# simplePDschematicsv2_AZ_SMD.net
KiCad netlist of a schematic drawn in EAGLE
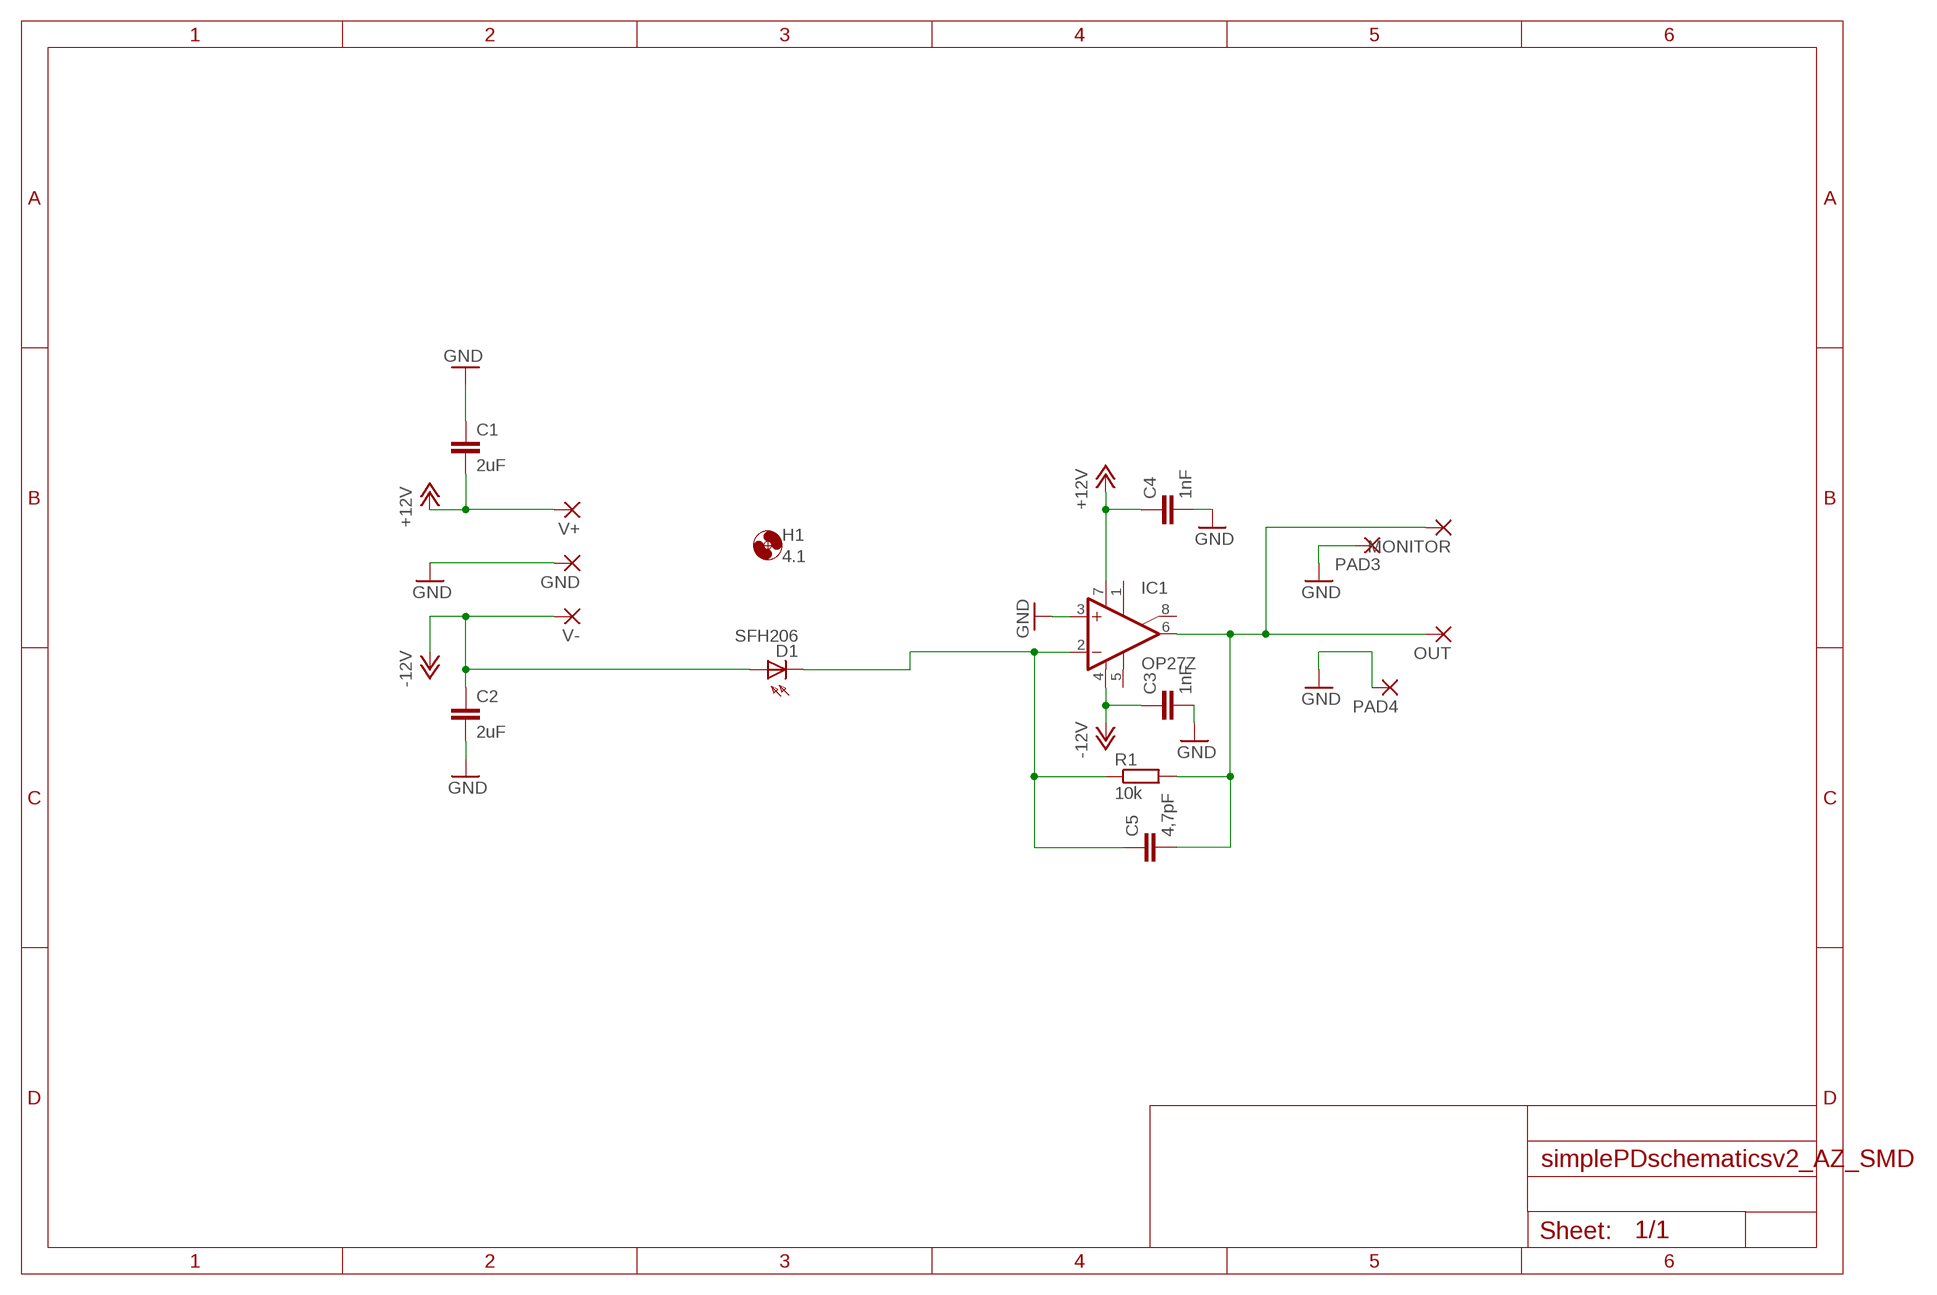
[diagram p0: schematic, sheet 1]

(export (version "E")
  (design (tool "Eeschema 10.0.6"))
  (components
    (comp (ref "C1")
      (value "2uF")
      (footprint "eagle-import:C050-075X075")
      (libsource (lib "eagle-import") (part "C-EU050-075X075"))
    )
    (comp (ref "C2")
      (value "2uF")
      (footprint "eagle-import:C050-075X075")
      (libsource (lib "eagle-import") (part "C-EU050-075X075"))
    )
    (comp (ref "C3")
      (value "1nF")
      (footprint "eagle-import:C025-050X050")
      (libsource (lib "eagle-import") (part "C-EU025-050X050"))
    )
    (comp (ref "C4")
      (value "1nF")
      (footprint "eagle-import:C025-050X050")
      (libsource (lib "eagle-import") (part "C-EU025-050X050"))
    )
    (comp (ref "C5")
      (value "4,7pF")
      (footprint "eagle-import:C025-050X050")
      (libsource (lib "eagle-import") (part "C-EU025-050X050"))
    )
    (comp (ref "D1")
      (value "SFH206")
      (footprint "eagle-import:SFH206")
      (fields (field (name "MPN") "SFH206K"))
      (libsource (lib "eagle-import") (part "SFH206"))
    )
    (comp (ref "GND")
      (value "1,6/0,9")
      (footprint "eagle-import:1,6_0,9")
      (libsource (lib "eagle-import") (part "1,6/0,9"))
    )
    (comp (ref "H1")
      (value "4.1")
      (footprint "eagle-import:4,1")
      (libsource (lib "eagle-import") (part "MOUNT-HOLE4.1"))
    )
    (comp (ref "IC1")
      (value "OP27Z")
      (footprint "eagle-import:DIL08")
      (libsource (lib "eagle-import") (part "OP27Z"))
    )
    (comp (ref "MONITOR")
      (value "1,6/0,9")
      (footprint "eagle-import:1,6_0,9")
      (libsource (lib "eagle-import") (part "1,6/0,9"))
    )
    (comp (ref "OUT")
      (value "1,6/0,9")
      (footprint "eagle-import:1,6_0,9")
      (libsource (lib "eagle-import") (part "1,6/0,9"))
    )
    (comp (ref "PAD3")
      (value "1,6/0,9")
      (footprint "eagle-import:1,6_0,9")
      (libsource (lib "eagle-import") (part "1,6/0,9"))
    )
    (comp (ref "PAD4")
      (value "1,6/0,9")
      (footprint "eagle-import:1,6_0,9")
      (libsource (lib "eagle-import") (part "1,6/0,9"))
    )
    (comp (ref "R1")
      (value "10k")
      (footprint "eagle-import:M1206")
      (libsource (lib "eagle-import") (part "R-EU_M1206"))
    )
    (comp (ref "V+")
      (value "1,6/0,9")
      (footprint "eagle-import:1,6_0,9")
      (libsource (lib "eagle-import") (part "1,6/0,9"))
    )
    (comp (ref "V-")
      (value "1,6/0,9")
      (footprint "eagle-import:1,6_0,9")
      (libsource (lib "eagle-import") (part "1,6/0,9"))
    )
  )
  (nets
    (net (code "1") (name "+12V") (class "Default")
      (node (ref "C1") (pin "2") (pinfunction "2_2") (pintype "passive"))
      (node (ref "C4") (pin "1") (pinfunction "1_1") (pintype "passive"))
      (node (ref "IC1") (pin "7") (pinfunction "V+_7") (pintype "power_in"))
      (node (ref "V+") (pin "1") (pinfunction "P_1") (pintype "passive"))
    )
    (net (code "2") (name "-12V") (class "Default")
      (node (ref "C2") (pin "1") (pinfunction "1_1") (pintype "passive"))
      (node (ref "C3") (pin "1") (pinfunction "1_1") (pintype "passive"))
      (node (ref "D1") (pin "A") (pinfunction "A_A") (pintype "passive"))
      (node (ref "IC1") (pin "4") (pinfunction "V-_4") (pintype "power_in"))
      (node (ref "V-") (pin "1") (pinfunction "P_1") (pintype "passive"))
    )
    (net (code "3") (name "GND") (class "Default")
      (node (ref "C1") (pin "1") (pinfunction "1_1") (pintype "passive"))
      (node (ref "C2") (pin "2") (pinfunction "2_2") (pintype "passive"))
      (node (ref "C3") (pin "2") (pinfunction "2_2") (pintype "passive"))
      (node (ref "C4") (pin "2") (pinfunction "2_2") (pintype "passive"))
      (node (ref "GND") (pin "1") (pinfunction "P_1") (pintype "passive"))
      (node (ref "IC1") (pin "3") (pinfunction "+IN_3") (pintype "input"))
      (node (ref "PAD3") (pin "1") (pinfunction "P_1") (pintype "passive"))
      (node (ref "PAD4") (pin "1") (pinfunction "P_1") (pintype "passive"))
    )
    (net (code "4") (name "Net-(D1-C)") (class "Default")
      (node (ref "C5") (pin "1") (pinfunction "1_1") (pintype "passive"))
      (node (ref "D1") (pin "K") (pinfunction "C_K") (pintype "passive"))
      (node (ref "IC1") (pin "2") (pinfunction "-IN_2") (pintype "input"))
      (node (ref "R1") (pin "1") (pinfunction "1_1") (pintype "passive"))
    )
    (net (code "5") (name "Net-(IC1-OUT)") (class "Default")
      (node (ref "C5") (pin "2") (pinfunction "2_2") (pintype "passive"))
      (node (ref "IC1") (pin "6") (pinfunction "OUT_6") (pintype "output"))
      (node (ref "MONITOR") (pin "1") (pinfunction "P_1") (pintype "passive"))
      (node (ref "OUT") (pin "1") (pinfunction "P_1") (pintype "passive"))
      (node (ref "R1") (pin "2") (pinfunction "2_2") (pintype "passive"))
    )
    (net (code "6") (name "unconnected-(IC1-ON1-Pad1)") (class "Default")
      (node (ref "IC1") (pin "1") (pinfunction "ON1_1") (pintype "passive"))
    )
    (net (code "7") (name "unconnected-(IC1-ON2-Pad8)") (class "Default")
      (node (ref "IC1") (pin "8") (pinfunction "ON2_8") (pintype "passive"))
    )
    (net (code "8") (name "unconnected-(IC1-OPT-Pad5)") (class "Default")
      (node (ref "IC1") (pin "5") (pinfunction "OPT_5") (pintype "passive"))
    )
  )
)
